# STl-Link-V303-small.net
KiCad netlist of a schematic drawn in EAGLE
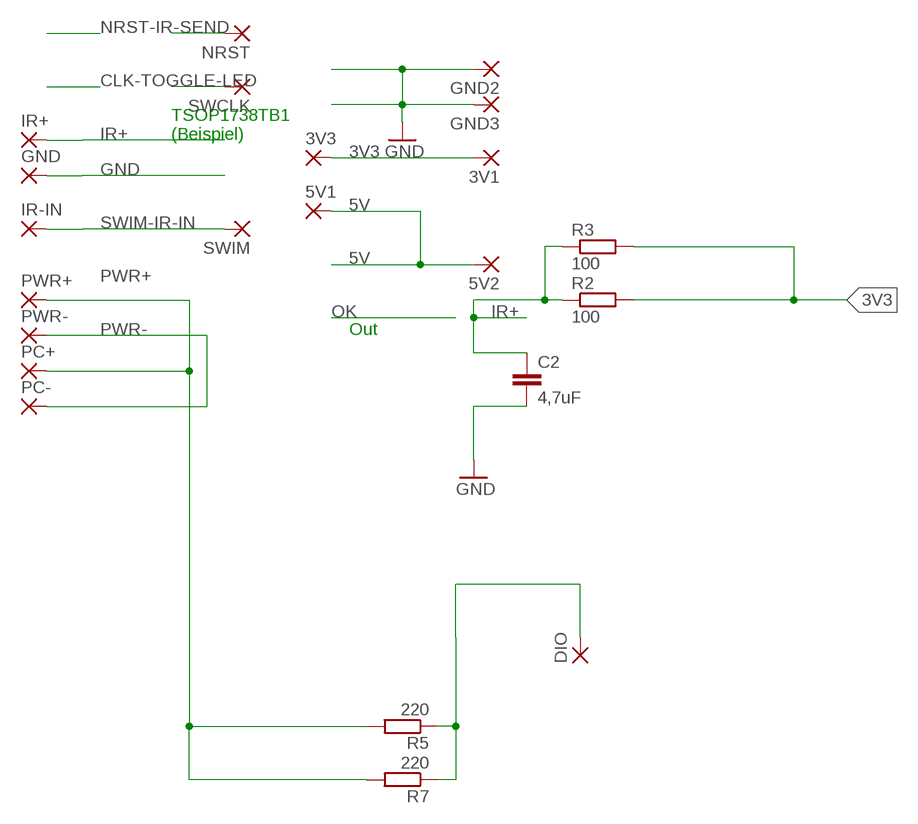
[diagram p0: schematic, sheet 1]

(export (version "E")
  (design (tool "Eeschema 10.0.6"))
  (components
    (comp (ref "3V1")
      (value "SMD2")
      (footprint "eagle-import:SMD1,27-2,54")
      (libsource (lib "eagle-import") (part "SMD2"))
    )
    (comp (ref "3V3")
      (value "SMD2")
      (footprint "eagle-import:SMD1,27-2,54")
      (libsource (lib "eagle-import") (part "SMD2"))
    )
    (comp (ref "5V1")
      (value "SMD2")
      (footprint "eagle-import:SMD1,27-2,54")
      (libsource (lib "eagle-import") (part "SMD2"))
    )
    (comp (ref "5V2")
      (value "SMD2")
      (footprint "eagle-import:SMD1,27-2,54")
      (libsource (lib "eagle-import") (part "SMD2"))
    )
    (comp (ref "C2")
      (value "4,7uF")
      (footprint "eagle-import:C1206K")
      (libsource (lib "eagle-import") (part "C-EUC1206K"))
    )
    (comp (ref "DIO")
      (value "SMD2")
      (footprint "eagle-import:SMD1,27-2,54")
      (libsource (lib "eagle-import") (part "SMD2"))
    )
    (comp (ref "GND")
      (value "SMD2")
      (footprint "eagle-import:SMD1,27-2,54")
      (libsource (lib "eagle-import") (part "SMD2"))
    )
    (comp (ref "GND2")
      (value "SMD2")
      (footprint "eagle-import:SMD1,27-2,54")
      (libsource (lib "eagle-import") (part "SMD2"))
    )
    (comp (ref "GND3")
      (value "SMD2")
      (footprint "eagle-import:SMD1,27-2,54")
      (libsource (lib "eagle-import") (part "SMD2"))
    )
    (comp (ref "IR+")
      (value "SMD2")
      (footprint "eagle-import:SMD1,27-2,54")
      (libsource (lib "eagle-import") (part "SMD2"))
    )
    (comp (ref "IR-IN")
      (value "SMD2")
      (footprint "eagle-import:SMD1,27-2,54")
      (libsource (lib "eagle-import") (part "SMD2"))
    )
    (comp (ref "NRST")
      (value "SMD2")
      (footprint "eagle-import:SMD1,27-2,54")
      (libsource (lib "eagle-import") (part "SMD2"))
    )
    (comp (ref "PC+")
      (value "SMD2")
      (footprint "eagle-import:SMD1,27-2,54")
      (libsource (lib "eagle-import") (part "SMD2"))
    )
    (comp (ref "PC-")
      (value "SMD2")
      (footprint "eagle-import:SMD1,27-2,54")
      (libsource (lib "eagle-import") (part "SMD2"))
    )
    (comp (ref "PWR+")
      (value "SMD2")
      (footprint "eagle-import:SMD1,27-2,54")
      (libsource (lib "eagle-import") (part "SMD2"))
    )
    (comp (ref "PWR-")
      (value "SMD2")
      (footprint "eagle-import:SMD1,27-2,54")
      (libsource (lib "eagle-import") (part "SMD2"))
    )
    (comp (ref "R2")
      (value "100")
      (footprint "eagle-import:0204_7")
      (libsource (lib "eagle-import") (part "R-EU_0204/7"))
    )
    (comp (ref "R3")
      (value "100")
      (footprint "eagle-import:R0805W")
      (libsource (lib "eagle-import") (part "R-EU_R0805W"))
    )
    (comp (ref "R5")
      (value "220")
      (footprint "eagle-import:0204_7")
      (libsource (lib "eagle-import") (part "R-EU_0204/7"))
    )
    (comp (ref "R7")
      (value "220")
      (footprint "eagle-import:R0805W")
      (libsource (lib "eagle-import") (part "R-EU_R0805W"))
    )
    (comp (ref "SWCLK")
      (value "SMD2")
      (footprint "eagle-import:SMD1,27-2,54")
      (libsource (lib "eagle-import") (part "SMD2"))
    )
    (comp (ref "SWIM")
      (value "SMD2")
      (footprint "eagle-import:SMD1,27-2,54")
      (libsource (lib "eagle-import") (part "SMD2"))
    )
  )
  (nets
    (net (code "1") (name "/5V") (class "Default")
      (node (ref "5V1") (pin "1") (pinfunction "P_1") (pintype "passive"))
      (node (ref "5V2") (pin "1") (pinfunction "P_1") (pintype "passive"))
    )
    (net (code "2") (name "/CLK-TOGGLE-LED") (class "Default")
      (node (ref "SWCLK") (pin "1") (pinfunction "P_1") (pintype "passive"))
    )
    (net (code "3") (name "/IR+") (class "Default")
      (node (ref "C2") (pin "1") (pinfunction "1_1") (pintype "passive"))
      (node (ref "IR+") (pin "1") (pinfunction "P_1") (pintype "passive"))
      (node (ref "R2") (pin "1") (pinfunction "1_1") (pintype "passive"))
      (node (ref "R3") (pin "1") (pinfunction "1_1") (pintype "passive"))
    )
    (net (code "6") (name "/PWR+") (class "Default")
      (node (ref "PC+") (pin "1") (pinfunction "P_1") (pintype "passive"))
      (node (ref "PWR+") (pin "1") (pinfunction "P_1") (pintype "passive"))
      (node (ref "R5") (pin "2") (pinfunction "2_2") (pintype "passive"))
      (node (ref "R7") (pin "2") (pinfunction "2_2") (pintype "passive"))
    )
    (net (code "7") (name "/PWR-") (class "Default")
      (node (ref "PC-") (pin "1") (pinfunction "P_1") (pintype "passive"))
      (node (ref "PWR-") (pin "1") (pinfunction "P_1") (pintype "passive"))
    )
    (net (code "8") (name "/SWIM-IR-IN") (class "Default")
      (node (ref "IR-IN") (pin "1") (pinfunction "P_1") (pintype "passive"))
      (node (ref "SWIM") (pin "1") (pinfunction "P_1") (pintype "passive"))
    )
    (net (code "9") (name "3V3") (class "Default")
      (node (ref "3V1") (pin "1") (pinfunction "P_1") (pintype "passive"))
      (node (ref "3V3") (pin "1") (pinfunction "P_1") (pintype "passive"))
      (node (ref "R2") (pin "2") (pinfunction "2_2") (pintype "passive"))
      (node (ref "R3") (pin "2") (pinfunction "2_2") (pintype "passive"))
    )
    (net (code "10") (name "GND") (class "Default")
      (node (ref "C2") (pin "2") (pinfunction "2_2") (pintype "passive"))
      (node (ref "GND") (pin "1") (pinfunction "P_1") (pintype "passive"))
      (node (ref "GND2") (pin "1") (pinfunction "P_1") (pintype "passive"))
      (node (ref "GND3") (pin "1") (pinfunction "P_1") (pintype "passive"))
    )
    (net (code "11") (name "Net-(DIO-P)") (class "Default")
      (node (ref "DIO") (pin "1") (pinfunction "P_1") (pintype "passive"))
      (node (ref "R5") (pin "1") (pinfunction "1_1") (pintype "passive"))
      (node (ref "R7") (pin "1") (pinfunction "1_1") (pintype "passive"))
    )
    (net (code "12") (name "unconnected-(NRST-P-Pad1)") (class "Default")
      (node (ref "NRST") (pin "1") (pinfunction "P_1") (pintype "passive"))
    )
  )
)
